# IdcProbe.net
KiCad netlist of a schematic drawn in EAGLE
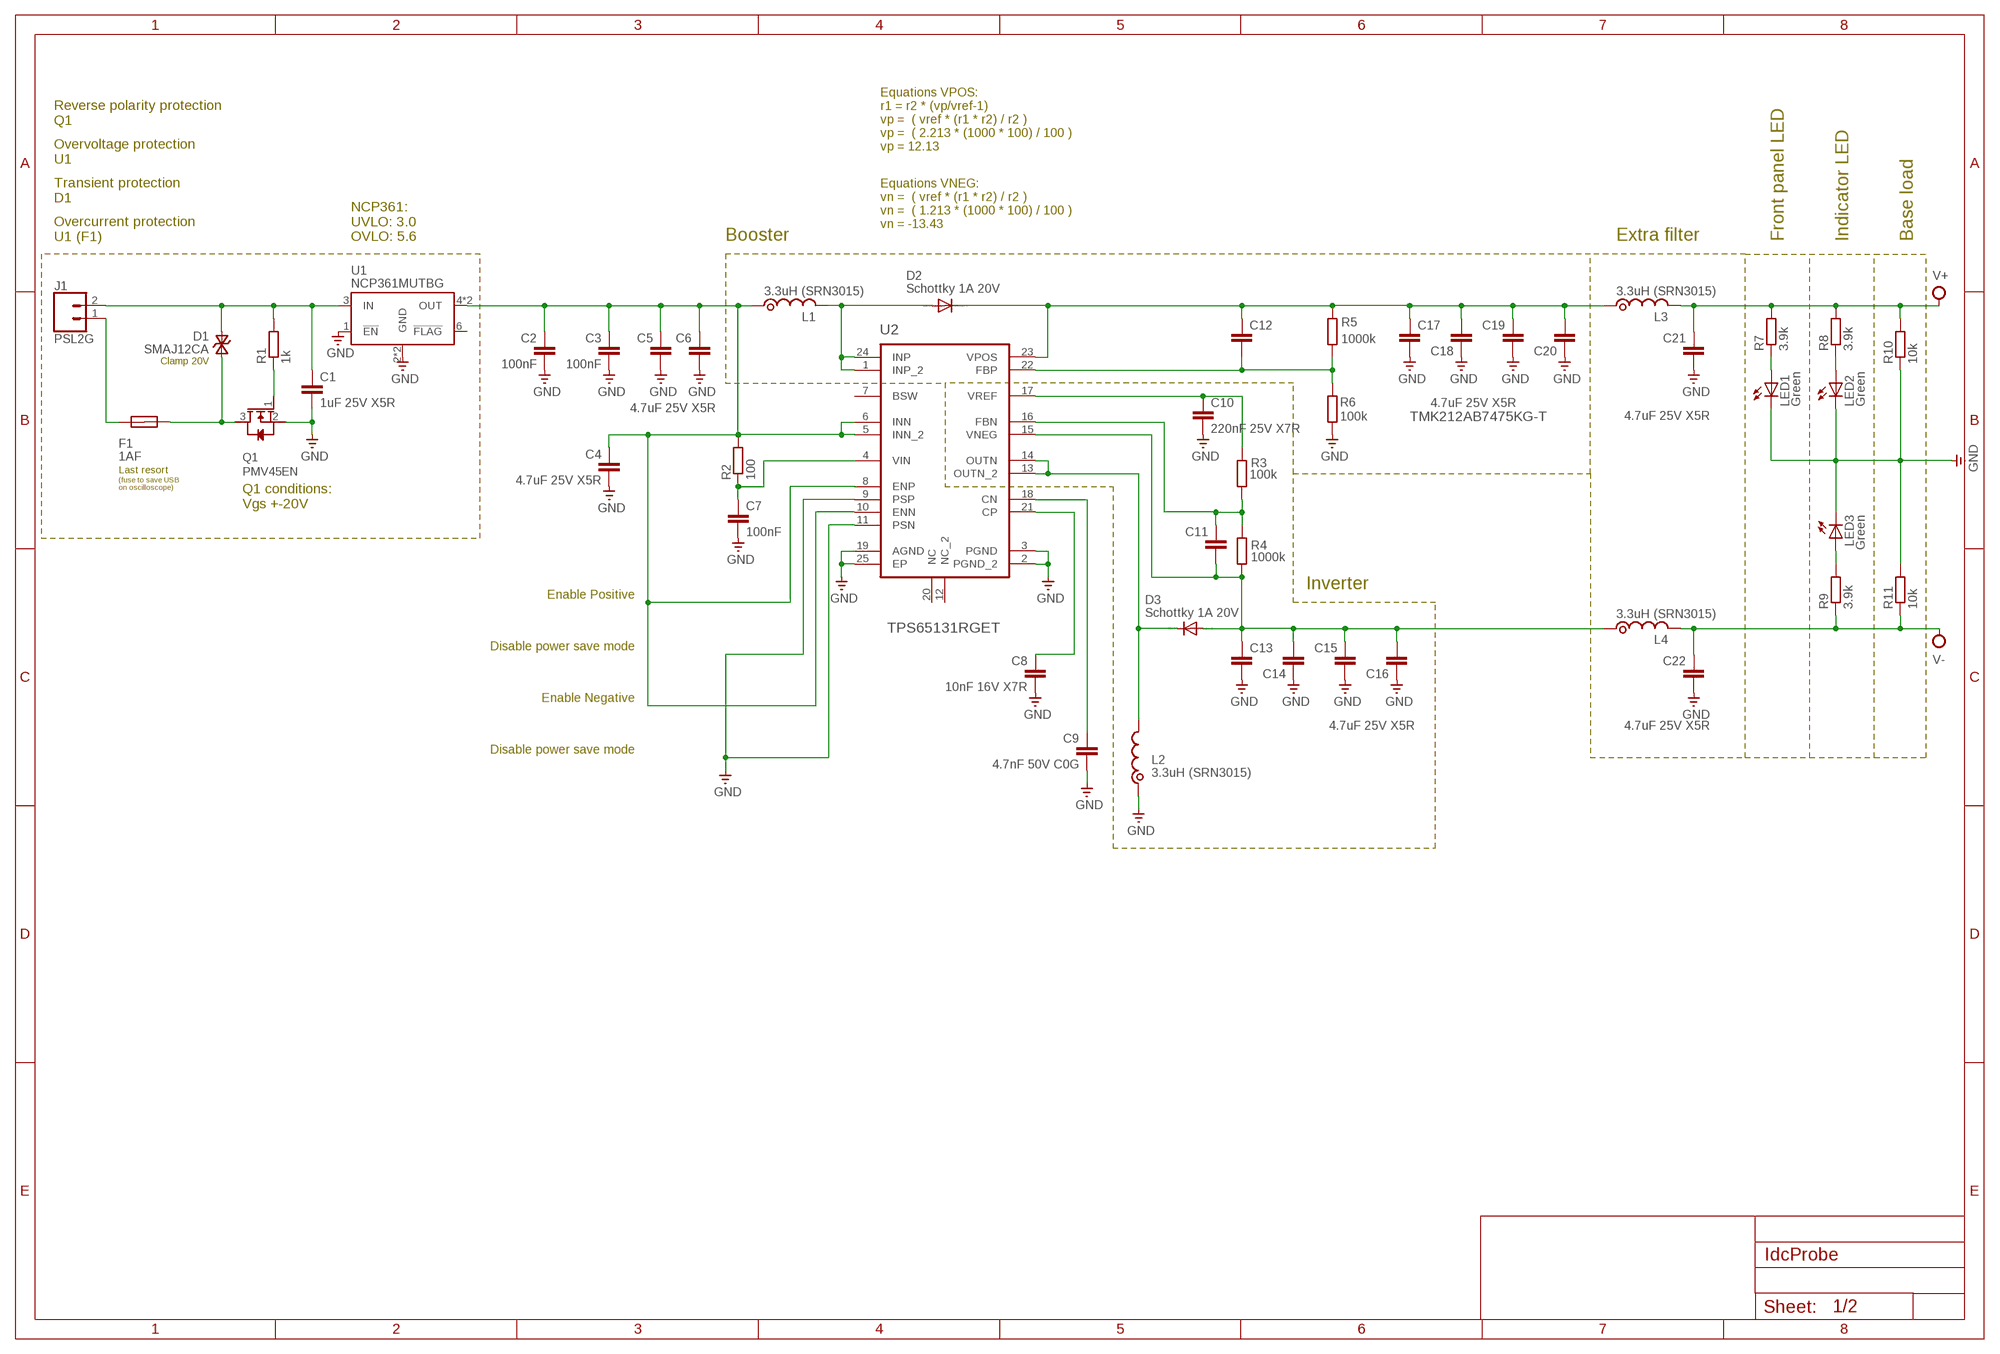
[diagram p0: schematic, sheet 1]
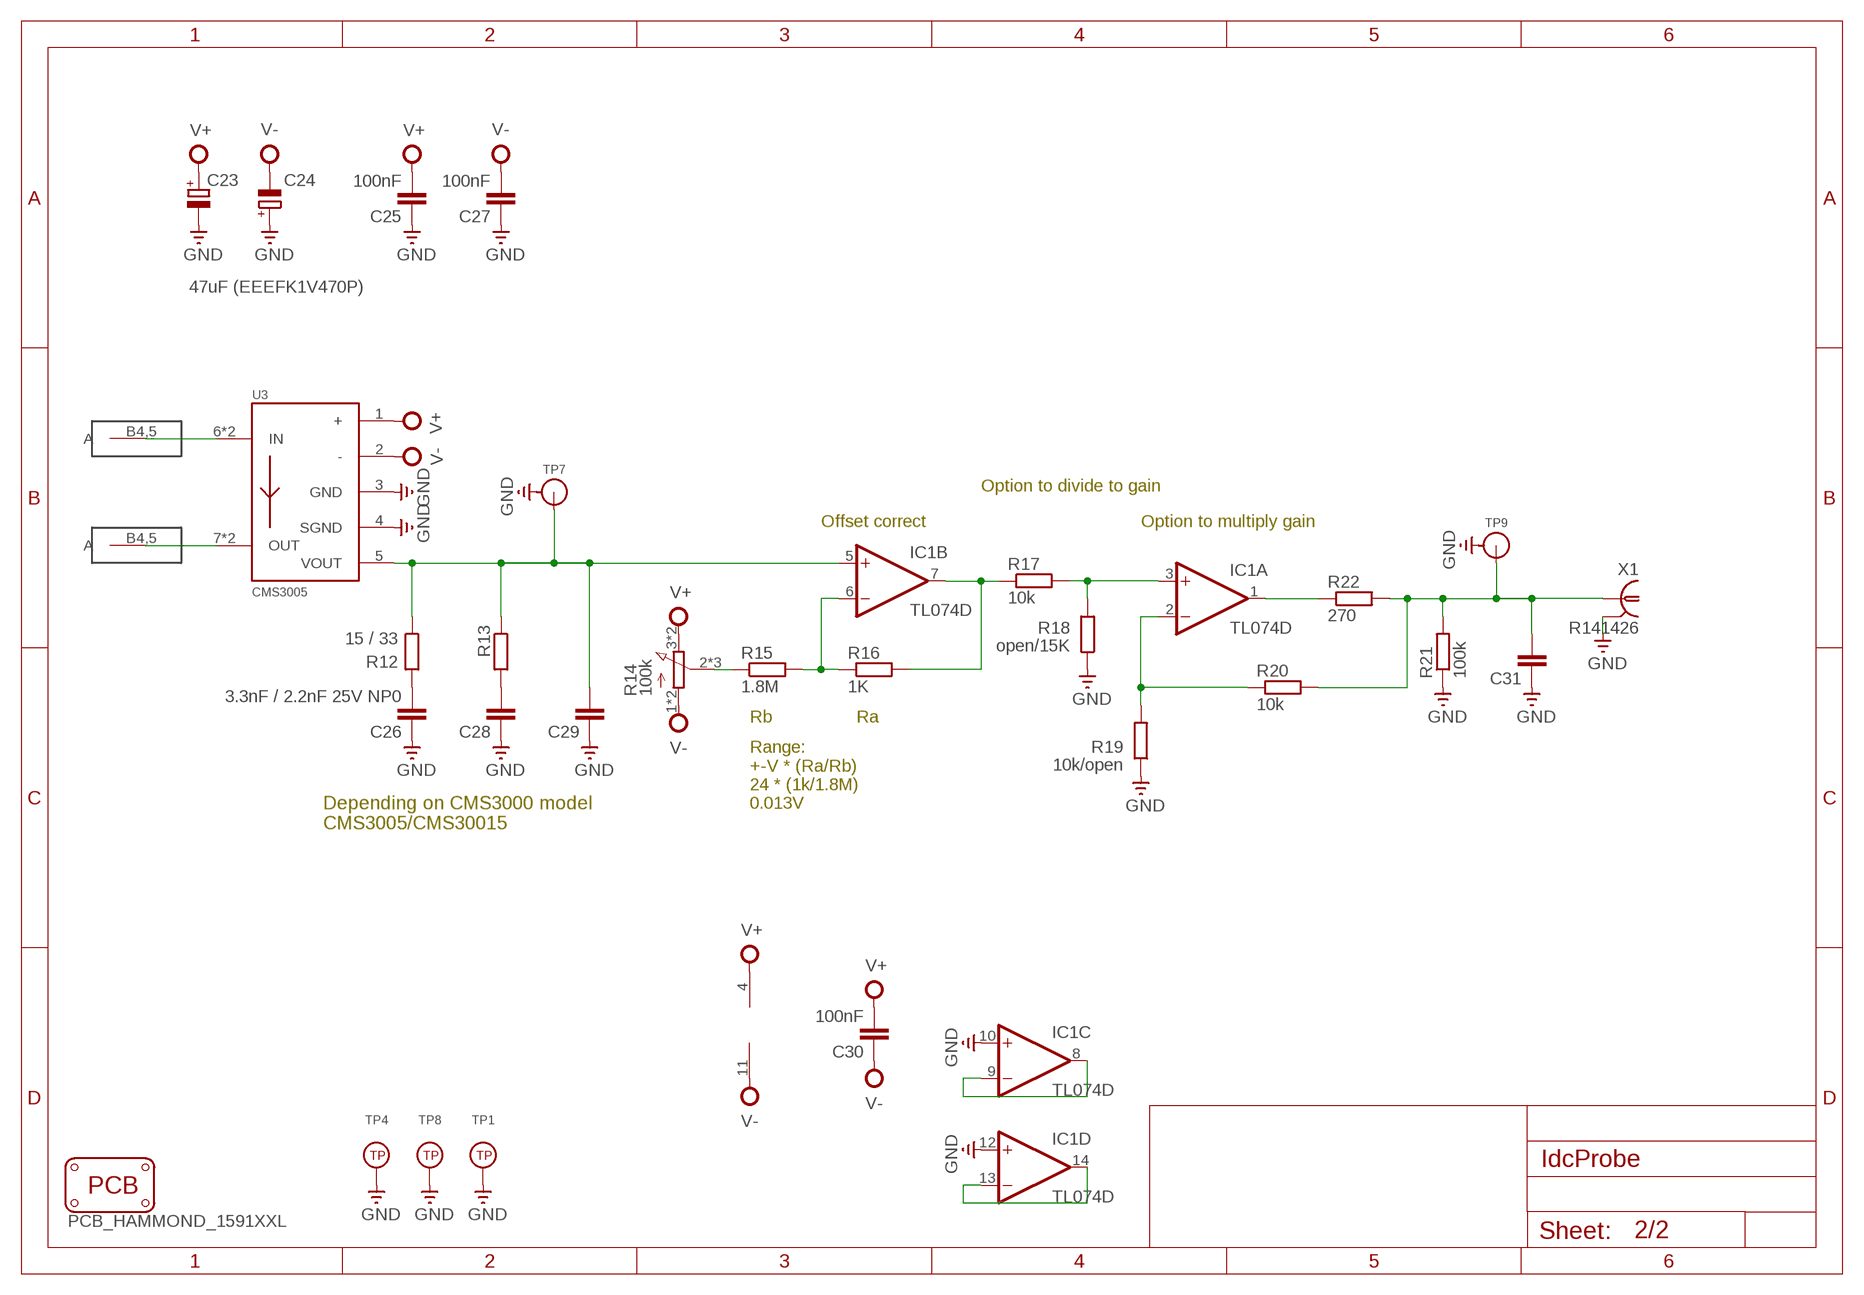
[diagram p1: schematic, sheet 2]

(export (version "E")
  (design (tool "Eeschema 10.0.6"))
  (components
    (comp (ref "C23")
      (value "47uF (EEEFK1V470P)")
      (footprint "eagle-import:PANASONIC_D")
      (libsource (lib "eagle-import") (part "CPOL-EUD"))
    )
    (comp (ref "C24")
      (value "47uF (EEEFK1V470P)")
      (footprint "eagle-import:PANASONIC_D")
      (libsource (lib "eagle-import") (part "CPOL-EUD"))
    )
    (comp (ref "C25")
      (value "100nF")
      (footprint "eagle-import:C0805")
      (libsource (lib "eagle-import") (part "C-EUC0805"))
    )
    (comp (ref "C26")
      (value "3.3nF / 2.2nF 25V NP0")
      (footprint "eagle-import:C0805")
      (libsource (lib "eagle-import") (part "C-EUC0805"))
    )
    (comp (ref "C27")
      (value "100nF")
      (footprint "eagle-import:C0805")
      (libsource (lib "eagle-import") (part "C-EUC0805"))
    )
    (comp (ref "C28")
      (value "C-EUC0805")
      (footprint "eagle-import:C0805")
      (libsource (lib "eagle-import") (part "C-EUC0805"))
    )
    (comp (ref "C29")
      (value "C-EUC0805")
      (footprint "eagle-import:C0805")
      (libsource (lib "eagle-import") (part "C-EUC0805"))
    )
    (comp (ref "C30")
      (value "100nF")
      (footprint "eagle-import:C0805")
      (libsource (lib "eagle-import") (part "C-EUC0805"))
    )
    (comp (ref "C31")
      (value "C-EUC0805")
      (footprint "eagle-import:C0805")
      (libsource (lib "eagle-import") (part "C-EUC0805"))
    )
    (comp (ref "H1")
      (value "PCB_HAMMOND_1591XXL")
      (footprint "eagle-import:HMD_MFG_1591XXL")
      (libsource (lib "eagle-import") (part "PCB_HAMMOND_1591XXL"))
    )
    (comp (ref "IC1")
      (value "TL074D")
      (footprint "eagle-import:SO14")
      (libsource (lib "eagle-import") (part "TL074D"))
    )
    (comp (ref "P1")
      (value "BANANA_SOCKETVERTICAL")
      (footprint "eagle-import:4,5-PAD")
      (libsource (lib "eagle-import") (part "BANANA_SOCKETVERTICAL"))
    )
    (comp (ref "P2")
      (value "BANANA_SOCKETVERTICAL")
      (footprint "eagle-import:4,5-PAD")
      (libsource (lib "eagle-import") (part "BANANA_SOCKETVERTICAL"))
    )
    (comp (ref "R12")
      (value "15 / 33")
      (footprint "eagle-import:R0805")
      (libsource (lib "eagle-import") (part "R-EU_R0805"))
    )
    (comp (ref "R13")
      (value "R-EU_R0805")
      (footprint "eagle-import:R0805")
      (libsource (lib "eagle-import") (part "R-EU_R0805"))
    )
    (comp (ref "R14")
      (value "100k")
      (footprint "eagle-import:3386-MULTI")
      (fields (field (name "MPN") "3386P-1-104LF"))
      (libsource (lib "eagle-import") (part "POT_MULTI"))
    )
    (comp (ref "R15")
      (value "1.8M")
      (footprint "eagle-import:R0805")
      (libsource (lib "eagle-import") (part "R-EU_R0805"))
    )
    (comp (ref "R16")
      (value "1K")
      (footprint "eagle-import:R0805")
      (libsource (lib "eagle-import") (part "R-EU_R0805"))
    )
    (comp (ref "R17")
      (value "10k")
      (footprint "eagle-import:R0805I")
      (libsource (lib "eagle-import") (part "R-EU_R0805I"))
    )
    (comp (ref "R18")
      (value "open/15K")
      (footprint "eagle-import:R0805I")
      (libsource (lib "eagle-import") (part "R-EU_R0805I"))
    )
    (comp (ref "R19")
      (value "10k/open")
      (footprint "eagle-import:R0805I")
      (libsource (lib "eagle-import") (part "R-EU_R0805I"))
    )
    (comp (ref "R20")
      (value "10k")
      (footprint "eagle-import:R0805I")
      (libsource (lib "eagle-import") (part "R-EU_R0805I"))
    )
    (comp (ref "R21")
      (value "100k")
      (footprint "eagle-import:R0805")
      (libsource (lib "eagle-import") (part "R-EU_R0805"))
    )
    (comp (ref "R22")
      (value "270")
      (footprint "eagle-import:R0805")
      (libsource (lib "eagle-import") (part "R-EU_R0805"))
    )
    (comp (ref "TP1")
      (value "TESTPOINT")
      (footprint "eagle-import:TESTHOOK")
      (libsource (lib "eagle-import") (part "TESTPOINT"))
    )
    (comp (ref "TP4")
      (value "TESTPOINT")
      (footprint "eagle-import:TESTHOOK")
      (libsource (lib "eagle-import") (part "TESTPOINT"))
    )
    (comp (ref "TP7")
      (value "TESTPOINT_GND")
      (footprint "eagle-import:PROBE_POINT")
      (libsource (lib "eagle-import") (part "TESTPOINT_GND"))
    )
    (comp (ref "TP8")
      (value "TESTPOINT")
      (footprint "eagle-import:TESTHOOK")
      (libsource (lib "eagle-import") (part "TESTPOINT"))
    )
    (comp (ref "TP9")
      (value "TESTPOINT_GND")
      (footprint "eagle-import:PROBE_POINT")
      (libsource (lib "eagle-import") (part "TESTPOINT_GND"))
    )
    (comp (ref "U3")
      (value "CMS3005")
      (footprint "eagle-import:CMS3015")
      (libsource (lib "eagle-import") (part "CMS3000_15A"))
    )
    (comp (ref "X1")
      (value "R141426")
      (footprint "eagle-import:R141426")
      (fields (field (name "MF") "FARNELL") (field (name "MPN") "R141426161"))
      (libsource (lib "eagle-import") (part "R141426"))
    )
    (comp (ref "C1")
      (value "1uF 25V X5R")
      (footprint "eagle-import:C0805")
      (fields (field (name "MPN") "TMK212AB7475KG-T"))
      (libsource (lib "eagle-import") (part "C-EUC0805"))
    )
    (comp (ref "C2")
      (value "100nF")
      (footprint "eagle-import:C0805")
      (libsource (lib "eagle-import") (part "C-EUC0805"))
    )
    (comp (ref "C3")
      (value "100nF")
      (footprint "eagle-import:C0805")
      (libsource (lib "eagle-import") (part "C-EUC0805"))
    )
    (comp (ref "C4")
      (value "4.7uF 25V X5R")
      (footprint "eagle-import:C0805")
      (fields (field (name "MPN") "TMK212AB7475KG-T"))
      (libsource (lib "eagle-import") (part "C-EUC0805"))
    )
    (comp (ref "C5")
      (value "4.7uF 25V X5R")
      (footprint "eagle-import:C0805")
      (fields (field (name "MPN") "TMK212AB7475KG-T"))
      (libsource (lib "eagle-import") (part "C-EUC0805"))
    )
    (comp (ref "C6")
      (value "4.7uF 25V X5R")
      (footprint "eagle-import:C0805")
      (fields (field (name "MPN") "TMK212AB7475KG-T"))
      (libsource (lib "eagle-import") (part "C-EUC0805"))
    )
    (comp (ref "C7")
      (value "100nF")
      (footprint "eagle-import:C0805")
      (libsource (lib "eagle-import") (part "C-EUC0805"))
    )
    (comp (ref "C8")
      (value "10nF 16V X7R")
      (footprint "eagle-import:C0805")
      (libsource (lib "eagle-import") (part "C-EUC0805"))
    )
    (comp (ref "C9")
      (value "4.7nF 50V C0G")
      (footprint "eagle-import:C0805")
      (libsource (lib "eagle-import") (part "C-EUC0805"))
    )
    (comp (ref "C10")
      (value "220nF 25V X7R")
      (footprint "eagle-import:C0805")
      (libsource (lib "eagle-import") (part "C-EUC0805"))
    )
    (comp (ref "C11")
      (value "C-EUC0805")
      (footprint "eagle-import:C0805")
      (libsource (lib "eagle-import") (part "C-EUC0805"))
    )
    (comp (ref "C12")
      (value "C-EUC0805")
      (footprint "eagle-import:C0805")
      (libsource (lib "eagle-import") (part "C-EUC0805"))
    )
    (comp (ref "C13")
      (value "4.7uF 25V X5R")
      (footprint "eagle-import:C0805")
      (fields (field (name "MPN") "TMK212AB7475KG-T"))
      (libsource (lib "eagle-import") (part "C-EUC0805"))
    )
    (comp (ref "C14")
      (value "4.7uF 25V X5R")
      (footprint "eagle-import:C0805")
      (fields (field (name "MPN") "TMK212AB7475KG-T"))
      (libsource (lib "eagle-import") (part "C-EUC0805"))
    )
    (comp (ref "C15")
      (value "4.7uF 25V X5R")
      (footprint "eagle-import:C0805")
      (fields (field (name "MPN") "TMK212AB7475KG-T"))
      (libsource (lib "eagle-import") (part "C-EUC0805"))
    )
    (comp (ref "C16")
      (value "4.7uF 25V X5R")
      (footprint "eagle-import:C0805")
      (fields (field (name "MPN") "TMK212AB7475KG-T"))
      (libsource (lib "eagle-import") (part "C-EUC0805"))
    )
    (comp (ref "C17")
      (value "4.7uF 25V X5R")
      (footprint "eagle-import:C0805")
      (fields (field (name "MPN") "TMK212AB7475KG-T"))
      (libsource (lib "eagle-import") (part "C-EUC0805"))
    )
    (comp (ref "C18")
      (value "4.7uF 25V X5R")
      (footprint "eagle-import:C0805")
      (fields (field (name "MPN") "TMK212AB7475KG-T"))
      (libsource (lib "eagle-import") (part "C-EUC0805"))
    )
    (comp (ref "C19")
      (value "4.7uF 25V X5R")
      (footprint "eagle-import:C0805")
      (fields (field (name "MPN") "TMK212AB7475KG-T"))
      (libsource (lib "eagle-import") (part "C-EUC0805"))
    )
    (comp (ref "C20")
      (value "4.7uF 25V X5R")
      (footprint "eagle-import:C0805")
      (fields (field (name "MPN") "TMK212AB7475KG-T"))
      (libsource (lib "eagle-import") (part "C-EUC0805"))
    )
    (comp (ref "C21")
      (value "4.7uF 25V X5R")
      (footprint "eagle-import:C0805")
      (fields (field (name "MPN") "TMK212AB7475KG-T"))
      (libsource (lib "eagle-import") (part "C-EUC0805"))
    )
    (comp (ref "C22")
      (value "4.7uF 25V X5R")
      (footprint "eagle-import:C0805")
      (fields (field (name "MPN") "TMK212AB7475KG-T"))
      (libsource (lib "eagle-import") (part "C-EUC0805"))
    )
    (comp (ref "D1")
      (value "SMAJ12CA")
      (footprint "eagle-import:SMA_NOPOL")
      (libsource (lib "eagle-import") (part "TVS_BISMA"))
    )
    (comp (ref "D2")
      (value "Schottky 1A 20V")
      (footprint "eagle-import:SOD323-R")
      (fields (field (name "MPN") "PMEG4010BEA"))
      (libsource (lib "eagle-import") (part "DIODE-SOD323-R"))
    )
    (comp (ref "D3")
      (value "Schottky 1A 20V")
      (footprint "eagle-import:SOD323-R")
      (fields (field (name "MPN") "PMEG4010BEA"))
      (libsource (lib "eagle-import") (part "DIODE-SOD323-R"))
    )
    (comp (ref "F1")
      (value "1AF")
      (footprint "eagle-import:1206_HV")
      (libsource (lib "eagle-import") (part "FUSE1206"))
    )
    (comp (ref "J1")
      (value "PSL2G")
      (footprint "eagle-import:MOLEX-1X2")
      (libsource (lib "eagle-import") (part "CONN_02POLAR"))
    )
    (comp (ref "L1")
      (value "3.3uH (SRN3015)")
      (footprint "eagle-import:VLS3015")
      (libsource (lib "eagle-import") (part "INDUCTOR_VLS3015"))
    )
    (comp (ref "L2")
      (value "3.3uH (SRN3015)")
      (footprint "eagle-import:VLS3015")
      (libsource (lib "eagle-import") (part "INDUCTOR_VLS3015"))
    )
    (comp (ref "L3")
      (value "3.3uH (SRN3015)")
      (footprint "eagle-import:VLS3015")
      (libsource (lib "eagle-import") (part "INDUCTOR_VLS3015"))
    )
    (comp (ref "L4")
      (value "3.3uH (SRN3015)")
      (footprint "eagle-import:VLS3015")
      (libsource (lib "eagle-import") (part "INDUCTOR_VLS3015"))
    )
    (comp (ref "LED1")
      (value "Green")
      (footprint "eagle-import:LED3MM")
      (libsource (lib "eagle-import") (part "LED3MM"))
    )
    (comp (ref "LED2")
      (value "Green")
      (footprint "eagle-import:CHIP-LED0805")
      (libsource (lib "eagle-import") (part "LEDCHIP-LED0805"))
    )
    (comp (ref "LED3")
      (value "Green")
      (footprint "eagle-import:CHIP-LED0805")
      (libsource (lib "eagle-import") (part "LEDCHIP-LED0805"))
    )
    (comp (ref "Q1")
      (value "PMV45EN")
      (footprint "eagle-import:SOT23")
      (libsource (lib "eagle-import") (part "PMV45EN"))
    )
    (comp (ref "R1")
      (value "1k")
      (footprint "eagle-import:R0805I")
      (libsource (lib "eagle-import") (part "R-EU_R0805I"))
    )
    (comp (ref "R2")
      (value "100")
      (footprint "eagle-import:R0805I")
      (libsource (lib "eagle-import") (part "R-EU_R0805I"))
    )
    (comp (ref "R3")
      (value "100k")
      (footprint "eagle-import:R0805I")
      (libsource (lib "eagle-import") (part "R-EU_R0805I"))
    )
    (comp (ref "R4")
      (value "1000k")
      (footprint "eagle-import:R0805I")
      (libsource (lib "eagle-import") (part "R-EU_R0805I"))
    )
    (comp (ref "R5")
      (value "1000k")
      (footprint "eagle-import:R0805I")
      (libsource (lib "eagle-import") (part "R-EU_R0805I"))
    )
    (comp (ref "R6")
      (value "100k")
      (footprint "eagle-import:R0805I")
      (libsource (lib "eagle-import") (part "R-EU_R0805I"))
    )
    (comp (ref "R7")
      (value "3.9k")
      (footprint "eagle-import:R0805I")
      (libsource (lib "eagle-import") (part "R-EU_R0805I"))
    )
    (comp (ref "R8")
      (value "3.9k")
      (footprint "eagle-import:R0805I")
      (libsource (lib "eagle-import") (part "R-EU_R0805I"))
    )
    (comp (ref "R9")
      (value "3.9k")
      (footprint "eagle-import:R0805I")
      (libsource (lib "eagle-import") (part "R-EU_R0805I"))
    )
    (comp (ref "R10")
      (value "10k")
      (footprint "eagle-import:R0805I")
      (libsource (lib "eagle-import") (part "R-EU_R0805I"))
    )
    (comp (ref "R11")
      (value "10k")
      (footprint "eagle-import:R0805I")
      (libsource (lib "eagle-import") (part "R-EU_R0805I"))
    )
    (comp (ref "U1")
      (value "NCP361MUTBG")
      (footprint "eagle-import:UDFN6_2X2")
      (fields (field (name "MPN") "TMK212AB7475KG-T"))
      (libsource (lib "eagle-import") (part "NCP36XMU"))
    )
    (comp (ref "U2")
      (value "TPS65131RGET")
      (footprint "eagle-import:QFN50P400X400X100-25N")
      (libsource (lib "eagle-import") (part "TPS65131RGET"))
    )
  )
  (nets
    (net (code "1") (name "GND") (class "Default")
      (node (ref "C1") (pin "2") (pinfunction "2_2") (pintype "passive"))
      (node (ref "C10") (pin "2") (pinfunction "2_2") (pintype "passive"))
      (node (ref "C13") (pin "2") (pinfunction "2_2") (pintype "passive"))
      (node (ref "C14") (pin "2") (pinfunction "2_2") (pintype "passive"))
      (node (ref "C15") (pin "2") (pinfunction "2_2") (pintype "passive"))
      (node (ref "C16") (pin "2") (pinfunction "2_2") (pintype "passive"))
      (node (ref "C17") (pin "2") (pinfunction "2_2") (pintype "passive"))
      (node (ref "C18") (pin "2") (pinfunction "2_2") (pintype "passive"))
      (node (ref "C19") (pin "2") (pinfunction "2_2") (pintype "passive"))
      (node (ref "C2") (pin "2") (pinfunction "2_2") (pintype "passive"))
      (node (ref "C20") (pin "2") (pinfunction "2_2") (pintype "passive"))
      (node (ref "C21") (pin "2") (pinfunction "2_2") (pintype "passive"))
      (node (ref "C22") (pin "2") (pinfunction "2_2") (pintype "passive"))
      (node (ref "C23") (pin "-") (pinfunction "-_-") (pintype "passive"))
      (node (ref "C24") (pin "+") (pinfunction "+_+") (pintype "passive"))
      (node (ref "C25") (pin "1") (pinfunction "1_1") (pintype "passive"))
      (node (ref "C26") (pin "1") (pinfunction "1_1") (pintype "passive"))
      (node (ref "C27") (pin "1") (pinfunction "1_1") (pintype "passive"))
      (node (ref "C28") (pin "1") (pinfunction "1_1") (pintype "passive"))
      (node (ref "C29") (pin "1") (pinfunction "1_1") (pintype "passive"))
      (node (ref "C3") (pin "2") (pinfunction "2_2") (pintype "passive"))
      (node (ref "C31") (pin "1") (pinfunction "1_1") (pintype "passive"))
      (node (ref "C4") (pin "2") (pinfunction "2_2") (pintype "passive"))
      (node (ref "C5") (pin "2") (pinfunction "2_2") (pintype "passive"))
      (node (ref "C6") (pin "2") (pinfunction "2_2") (pintype "passive"))
      (node (ref "C7") (pin "2") (pinfunction "2_2") (pintype "passive"))
      (node (ref "C8") (pin "2") (pinfunction "2_2") (pintype "passive"))
      (node (ref "C9") (pin "2") (pinfunction "2_2") (pintype "passive"))
      (node (ref "IC1") (pin "10") (pinfunction "+IN_10") (pintype "input"))
      (node (ref "IC1") (pin "12") (pinfunction "+IN_12") (pintype "input"))
      (node (ref "L2") (pin "1") (pinfunction "1_1") (pintype "passive"))
      (node (ref "LED1") (pin "K") (pinfunction "C_K") (pintype "passive"))
      (node (ref "LED2") (pin "C") (pinfunction "C_C") (pintype "passive"))
      (node (ref "LED3") (pin "C") (pinfunction "C_C") (pintype "passive"))
      (node (ref "Q1") (pin "2") (pinfunction "S_2") (pintype "bidirectional"))
      (node (ref "R10") (pin "1") (pinfunction "1_1") (pintype "passive"))
      (node (ref "R11") (pin "2") (pinfunction "2_2") (pintype "passive"))
      (node (ref "R18") (pin "1") (pinfunction "1_1") (pintype "passive"))
      (node (ref "R19") (pin "1") (pinfunction "1_1") (pintype "passive"))
      (node (ref "R21") (pin "1") (pinfunction "1_1") (pintype "passive"))
      (node (ref "R6") (pin "1") (pinfunction "1_1") (pintype "passive"))
      (node (ref "TP1") (pin "TP") (pinfunction "P$1_TP") (pintype "bidirectional"))
      (node (ref "TP4") (pin "TP") (pinfunction "P$1_TP") (pintype "bidirectional"))
      (node (ref "TP7") (pin "GND") (pinfunction "P$2_GND") (pintype "bidirectional"))
      (node (ref "TP8") (pin "TP") (pinfunction "P$1_TP") (pintype "bidirectional"))
      (node (ref "TP9") (pin "GND") (pinfunction "P$2_GND") (pintype "bidirectional"))
      (node (ref "U1") (pin "1") (pinfunction "~{EN}_1") (pintype "bidirectional"))
      (node (ref "U1") (pin "2") (pinfunction "GND_2") (pintype "bidirectional"))
      (node (ref "U1") (pin "7") (pinfunction "GND_7") (pintype "bidirectional"))
      (node (ref "U2") (pin "11") (pinfunction "PSN_11") (pintype "input"))
      (node (ref "U2") (pin "19") (pinfunction "AGND_19") (pintype "passive"))
      (node (ref "U2") (pin "2") (pinfunction "PGND_2_2") (pintype "passive"))
      (node (ref "U2") (pin "25") (pinfunction "EP_25") (pintype "passive"))
      (node (ref "U2") (pin "3") (pinfunction "PGND_3") (pintype "passive"))
      (node (ref "U2") (pin "9") (pinfunction "PSP_9") (pintype "input"))
      (node (ref "U3") (pin "3") (pinfunction "GND_3") (pintype "bidirectional"))
      (node (ref "U3") (pin "4") (pinfunction "SGND_4") (pintype "bidirectional"))
      (node (ref "X1") (pin "2") (pinfunction "2_2") (pintype "passive"))
      (node (ref "X1") (pin "3") (pinfunction "2_3") (pintype "passive"))
      (node (ref "X1") (pin "4") (pinfunction "2_4") (pintype "passive"))
      (node (ref "X1") (pin "5") (pinfunction "2_5") (pintype "passive"))
    )
    (net (code "2") (name "Net-(C26-Pad2)") (class "Default")
      (node (ref "C26") (pin "2") (pinfunction "2_2") (pintype "passive"))
      (node (ref "R12") (pin "2") (pinfunction "2_2") (pintype "passive"))
    )
    (net (code "3") (name "Net-(C28-Pad2)") (class "Default")
      (node (ref "C28") (pin "2") (pinfunction "2_2") (pintype "passive"))
      (node (ref "R13") (pin "2") (pinfunction "2_2") (pintype "passive"))
    )
    (net (code "4") (name "Net-(D1-A)") (class "Default")
      (node (ref "D1") (pin "1") (pinfunction "A_1") (pintype "passive"))
      (node (ref "F1") (pin "P$1") (pinfunction "P$1_P$1") (pintype "bidirectional"))
      (node (ref "Q1") (pin "3") (pinfunction "D_3") (pintype "bidirectional"))
    )
    (net (code "5") (name "Net-(D1-C)") (class "Default")
      (node (ref "C1") (pin "1") (pinfunction "1_1") (pintype "passive"))
      (node (ref "D1") (pin "2") (pinfunction "C_2") (pintype "passive"))
      (node (ref "J1") (pin "2") (pinfunction "2_2") (pintype "passive"))
      (node (ref "R1") (pin "2") (pinfunction "2_2") (pintype "passive"))
      (node (ref "U1") (pin "3") (pinfunction "IN_3") (pintype "bidirectional"))
    )
    (net (code "6") (name "Net-(F1-PadP$2)") (class "Default")
      (node (ref "F1") (pin "P$2") (pinfunction "P$2_P$2") (pintype "bidirectional"))
      (node (ref "J1") (pin "1") (pinfunction "1_1") (pintype "passive"))
    )
    (net (code "7") (name "Net-(IC1A-+IN)") (class "Default")
      (node (ref "IC1") (pin "3") (pinfunction "+IN_3") (pintype "input"))
      (node (ref "R17") (pin "2") (pinfunction "2_2") (pintype "passive"))
      (node (ref "R18") (pin "2") (pinfunction "2_2") (pintype "passive"))
    )
    (net (code "8") (name "Net-(IC1A--IN)") (class "Default")
      (node (ref "IC1") (pin "2") (pinfunction "-IN_2") (pintype "input"))
      (node (ref "R19") (pin "2") (pinfunction "2_2") (pintype "passive"))
      (node (ref "R20") (pin "1") (pinfunction "1_1") (pintype "passive"))
    )
    (net (code "9") (name "Net-(IC1A-OUT)") (class "Default")
      (node (ref "IC1") (pin "1") (pinfunction "OUT_1") (pintype "output"))
      (node (ref "R22") (pin "1") (pinfunction "1_1") (pintype "passive"))
    )
    (net (code "10") (name "Net-(IC1B-+IN)") (class "Default")
      (node (ref "C29") (pin "2") (pinfunction "2_2") (pintype "passive"))
      (node (ref "IC1") (pin "5") (pinfunction "+IN_5") (pintype "input"))
      (node (ref "R12") (pin "1") (pinfunction "1_1") (pintype "passive"))
      (node (ref "R13") (pin "1") (pinfunction "1_1") (pintype "passive"))
      (node (ref "TP7") (pin "TP") (pinfunction "P$1_TP") (pintype "bidirectional"))
      (node (ref "U3") (pin "5") (pinfunction "VOUT_5") (pintype "bidirectional"))
    )
    (net (code "11") (name "Net-(IC1B--IN)") (class "Default")
      (node (ref "IC1") (pin "6") (pinfunction "-IN_6") (pintype "input"))
      (node (ref "R15") (pin "2") (pinfunction "2_2") (pintype "passive"))
      (node (ref "R16") (pin "1") (pinfunction "1_1") (pintype "passive"))
    )
    (net (code "12") (name "Net-(IC1B-OUT)") (class "Default")
      (node (ref "IC1") (pin "7") (pinfunction "OUT_7") (pintype "output"))
      (node (ref "R16") (pin "2") (pinfunction "2_2") (pintype "passive"))
      (node (ref "R17") (pin "1") (pinfunction "1_1") (pintype "passive"))
    )
    (net (code "13") (name "Net-(IC1C--IN)") (class "Default")
      (node (ref "IC1") (pin "8") (pinfunction "OUT_8") (pintype "output"))
      (node (ref "IC1") (pin "9") (pinfunction "-IN_9") (pintype "input"))
    )
    (net (code "14") (name "Net-(IC1D--IN)") (class "Default")
      (node (ref "IC1") (pin "13") (pinfunction "-IN_13") (pintype "input"))
      (node (ref "IC1") (pin "14") (pinfunction "OUT_14") (pintype "output"))
    )
    (net (code "15") (name "Net-(LED1-PadA)") (class "Default")
      (node (ref "LED1") (pin "A") (pinfunction "A_A") (pintype "passive"))
      (node (ref "R7") (pin "1") (pinfunction "1_1") (pintype "passive"))
    )
    (net (code "16") (name "Net-(LED2-PadA)") (class "Default")
      (node (ref "LED2") (pin "A") (pinfunction "A_A") (pintype "passive"))
      (node (ref "R8") (pin "1") (pinfunction "1_1") (pintype "passive"))
    )
    (net (code "17") (name "Net-(LED3-PadA)") (class "Default")
      (node (ref "LED3") (pin "A") (pinfunction "A_A") (pintype "passive"))
      (node (ref "R9") (pin "2") (pinfunction "2_2") (pintype "passive"))
    )
    (net (code "18") (name "Net-(P1-A)") (class "Default")
      (node (ref "P1") (pin "B4,5") (pinfunction "A_B4,5") (pintype "bidirectional"))
      (node (ref "U3") (pin "6") (pinfunction "IN_6") (pintype "bidirectional"))
      (node (ref "U3") (pin "6'") (pinfunction "IN_6'") (pintype "bidirectional"))
    )
    (net (code "19") (name "Net-(P2-A)") (class "Default")
      (node (ref "P2") (pin "B4,5") (pinfunction "A_B4,5") (pintype "bidirectional"))
      (node (ref "U3") (pin "7") (pinfunction "OUT_7") (pintype "bidirectional"))
      (node (ref "U3") (pin "7'") (pinfunction "OUT_7'") (pintype "bidirectional"))
    )
    (net (code "20") (name "Net-(Q1-G)") (class "Default")
      (node (ref "Q1") (pin "1") (pinfunction "G_1") (pintype "bidirectional"))
      (node (ref "R1") (pin "1") (pinfunction "1_1") (pintype "passive"))
    )
    (net (code "21") (name "Net-(R14-SW-Pad2)") (class "Default")
      (node (ref "R14") (pin "2") (pinfunction "SW_2") (pintype "passive"))
      (node (ref "R14") (pin "5") (pinfunction "SW_5") (pintype "passive"))
      (node (ref "R14") (pin "7") (pinfunction "SW_7") (pintype "passive"))
      (node (ref "R15") (pin "1") (pinfunction "1_1") (pintype "passive"))
    )
    (net (code "22") (name "Net-(TP9-P$1)") (class "Default")
      (node (ref "C31") (pin "2") (pinfunction "2_2") (pintype "passive"))
      (node (ref "R20") (pin "2") (pinfunction "2_2") (pintype "passive"))
      (node (ref "R21") (pin "2") (pinfunction "2_2") (pintype "passive"))
      (node (ref "R22") (pin "2") (pinfunction "2_2") (pintype "passive"))
      (node (ref "TP9") (pin "TP") (pinfunction "P$1_TP") (pintype "bidirectional"))
      (node (ref "X1") (pin "1") (pinfunction "1_1") (pintype "passive"))
    )
    (net (code "23") (name "Net-(U2-CN)") (class "Default")
      (node (ref "C9") (pin "1") (pinfunction "1_1") (pintype "passive"))
      (node (ref "U2") (pin "18") (pinfunction "CN_18") (pintype "input"))
    )
    (net (code "24") (name "Net-(U2-CP)") (class "Default")
      (node (ref "C8") (pin "1") (pinfunction "1_1") (pintype "passive"))
      (node (ref "U2") (pin "21") (pinfunction "CP_21") (pintype "input"))
    )
    (net (code "25") (name "Net-(U2-ENN)") (class "Default")
      (node (ref "C2") (pin "1") (pinfunction "1_1") (pintype "passive"))
      (node (ref "C3") (pin "1") (pinfunction "1_1") (pintype "passive"))
      (node (ref "C4") (pin "1") (pinfunction "1_1") (pintype "passive"))
      (node (ref "C5") (pin "1") (pinfunction "1_1") (pintype "passive"))
      (node (ref "C6") (pin "1") (pinfunction "1_1") (pintype "passive"))
      (node (ref "L1") (pin "1") (pinfunction "1_1") (pintype "passive"))
      (node (ref "R2") (pin "2") (pinfunction "2_2") (pintype "passive"))
      (node (ref "U1") (pin "4") (pinfunction "OUT_4") (pintype "bidirectional"))
      (node (ref "U1") (pin "5") (pinfunction "OUT_5") (pintype "bidirectional"))
      (node (ref "U2") (pin "10") (pinfunction "ENN_10") (pintype "input"))
      (node (ref "U2") (pin "5") (pinfunction "INN_2_5") (pintype "input"))
      (node (ref "U2") (pin "6") (pinfunction "INN_6") (pintype "input"))
      (node (ref "U2") (pin "8") (pinfunction "ENP_8") (pintype "input"))
    )
    (net (code "26") (name "Net-(U2-FBN)") (class "Default")
      (node (ref "C11") (pin "1") (pinfunction "1_1") (pintype "passive"))
      (node (ref "R3") (pin "1") (pinfunction "1_1") (pintype "passive"))
      (node (ref "R4") (pin "1") (pinfunction "1_1") (pintype "passive"))
      (node (ref "U2") (pin "16") (pinfunction "FBN_16") (pintype "input"))
    )
    (net (code "27") (name "Net-(U2-FBP)") (class "Default")
      (node (ref "C12") (pin "2") (pinfunction "2_2") (pintype "passive"))
      (node (ref "R5") (pin "1") (pinfunction "1_1") (pintype "passive"))
      (node (ref "R6") (pin "2") (pinfunction "2_2") (pintype "passive"))
      (node (ref "U2") (pin "22") (pinfunction "FBP_22") (pintype "input"))
    )
    (net (code "28") (name "Net-(U2-INP)") (class "Default")
      (node (ref "D2") (pin "A") (pinfunction "A_A") (pintype "passive"))
      (node (ref "L1") (pin "2") (pinfunction "2_2") (pintype "passive"))
      (node (ref "U2") (pin "1") (pinfunction "INP_2_1") (pintype "input"))
      (node (ref "U2") (pin "24") (pinfunction "INP_24") (pintype "input"))
    )
    (net (code "29") (name "Net-(U2-OUTN)") (class "Default")
      (node (ref "D3") (pin "C") (pinfunction "C_C") (pintype "passive"))
      (node (ref "L2") (pin "2") (pinfunction "2_2") (pintype "passive"))
      (node (ref "U2") (pin "13") (pinfunction "OUTN_2_13") (pintype "output"))
      (node (ref "U2") (pin "14") (pinfunction "OUTN_14") (pintype "output"))
    )
    (net (code "30") (name "Net-(U2-VIN)") (class "Default")
      (node (ref "C7") (pin "1") (pinfunction "1_1") (pintype "passive"))
      (node (ref "R2") (pin "1") (pinfunction "1_1") (pintype "passive"))
      (node (ref "U2") (pin "4") (pinfunction "VIN_4") (pintype "power_in"))
    )
    (net (code "31") (name "Net-(U2-VNEG)") (class "Default")
      (node (ref "C11") (pin "2") (pinfunction "2_2") (pintype "passive"))
      (node (ref "C13") (pin "1") (pinfunction "1_1") (pintype "passive"))
      (node (ref "C14") (pin "1") (pinfunction "1_1") (pintype "passive"))
      (node (ref "C15") (pin "1") (pinfunction "1_1") (pintype "passive"))
      (node (ref "C16") (pin "1") (pinfunction "1_1") (pintype "passive"))
      (node (ref "D3") (pin "A") (pinfunction "A_A") (pintype "passive"))
      (node (ref "L4") (pin "1") (pinfunction "1_1") (pintype "passive"))
      (node (ref "R4") (pin "2") (pinfunction "2_2") (pintype "passive"))
      (node (ref "U2") (pin "15") (pinfunction "VNEG_15") (pintype "input"))
    )
    (net (code "32") (name "Net-(U2-VPOS)") (class "Default")
      (node (ref "C12") (pin "1") (pinfunction "1_1") (pintype "passive"))
      (node (ref "C17") (pin "1") (pinfunction "1_1") (pintype "passive"))
      (node (ref "C18") (pin "1") (pinfunction "1_1") (pintype "passive"))
      (node (ref "C19") (pin "1") (pinfunction "1_1") (pintype "passive"))
      (node (ref "C20") (pin "1") (pinfunction "1_1") (pintype "passive"))
      (node (ref "D2") (pin "C") (pinfunction "C_C") (pintype "passive"))
      (node (ref "L3") (pin "1") (pinfunction "1_1") (pintype "passive"))
      (node (ref "R5") (pin "2") (pinfunction "2_2") (pintype "passive"))
      (node (ref "U2") (pin "23") (pinfunction "VPOS_23") (pintype "input"))
    )
    (net (code "33") (name "Net-(U2-VREF)") (class "Default")
      (node (ref "C10") (pin "1") (pinfunction "1_1") (pintype "passive"))
      (node (ref "R3") (pin "2") (pinfunction "2_2") (pintype "passive"))
      (node (ref "U2") (pin "17") (pinfunction "VREF_17") (pintype "output"))
    )
    (net (code "34") (name "V+") (class "Default")
      (node (ref "C21") (pin "1") (pinfunction "1_1") (pintype "passive"))
      (node (ref "C23") (pin "+") (pinfunction "+_+") (pintype "passive"))
      (node (ref "C25") (pin "2") (pinfunction "2_2") (pintype "passive"))
      (node (ref "C30") (pin "2") (pinfunction "2_2") (pintype "passive"))
      (node (ref "IC1") (pin "4") (pinfunction "V+_4") (pintype "power_in"))
      (node (ref "L3") (pin "2") (pinfunction "2_2") (pintype "passive"))
      (node (ref "R10") (pin "2") (pinfunction "2_2") (pintype "passive"))
      (node (ref "R14") (pin "3") (pinfunction "CW_3") (pintype "passive"))
      (node (ref "R14") (pin "6") (pinfunction "CW_6") (pintype "passive"))
      (node (ref "R7") (pin "2") (pinfunction "2_2") (pintype "passive"))
      (node (ref "R8") (pin "2") (pinfunction "2_2") (pintype "passive"))
      (node (ref "U3") (pin "1") (pinfunction "+_1") (pintype "bidirectional"))
    )
    (net (code "35") (name "V-") (class "Default")
      (node (ref "C22") (pin "1") (pinfunction "1_1") (pintype "passive"))
      (node (ref "C24") (pin "-") (pinfunction "-_-") (pintype "passive"))
      (node (ref "C27") (pin "2") (pinfunction "2_2") (pintype "passive"))
      (node (ref "C30") (pin "1") (pinfunction "1_1") (pintype "passive"))
      (node (ref "IC1") (pin "11") (pinfunction "V-_11") (pintype "power_in"))
      (node (ref "L4") (pin "2") (pinfunction "2_2") (pintype "passive"))
      (node (ref "R11") (pin "1") (pinfunction "1_1") (pintype "passive"))
      (node (ref "R14") (pin "1") (pinfunction "CCW_1") (pintype "passive"))
      (node (ref "R14") (pin "4") (pinfunction "CCW_4") (pintype "passive"))
      (node (ref "R9") (pin "1") (pinfunction "1_1") (pintype "passive"))
      (node (ref "U3") (pin "2") (pinfunction "-_2") (pintype "bidirectional"))
    )
    (net (code "36") (name "unconnected-(U1-~{FLAG}-Pad6)") (class "Default")
      (node (ref "U1") (pin "6") (pinfunction "~{FLAG}_6") (pintype "bidirectional"))
    )
    (net (code "37") (name "unconnected-(U2-BSW-Pad7)") (class "Default")
      (node (ref "U2") (pin "7") (pinfunction "BSW_7") (pintype "output"))
    )
    (net (code "38") (name "unconnected-(U2-NC-Pad20)") (class "Default")
      (node (ref "U2") (pin "20") (pinfunction "NC_20") (pintype "no_connect"))
    )
    (net (code "39") (name "unconnected-(U2-NC_2-Pad12)") (class "Default")
      (node (ref "U2") (pin "12") (pinfunction "NC_2_12") (pintype "no_connect"))
    )
  )
)
